# HV-PCB.net
KiCad netlist of a schematic drawn in EAGLE
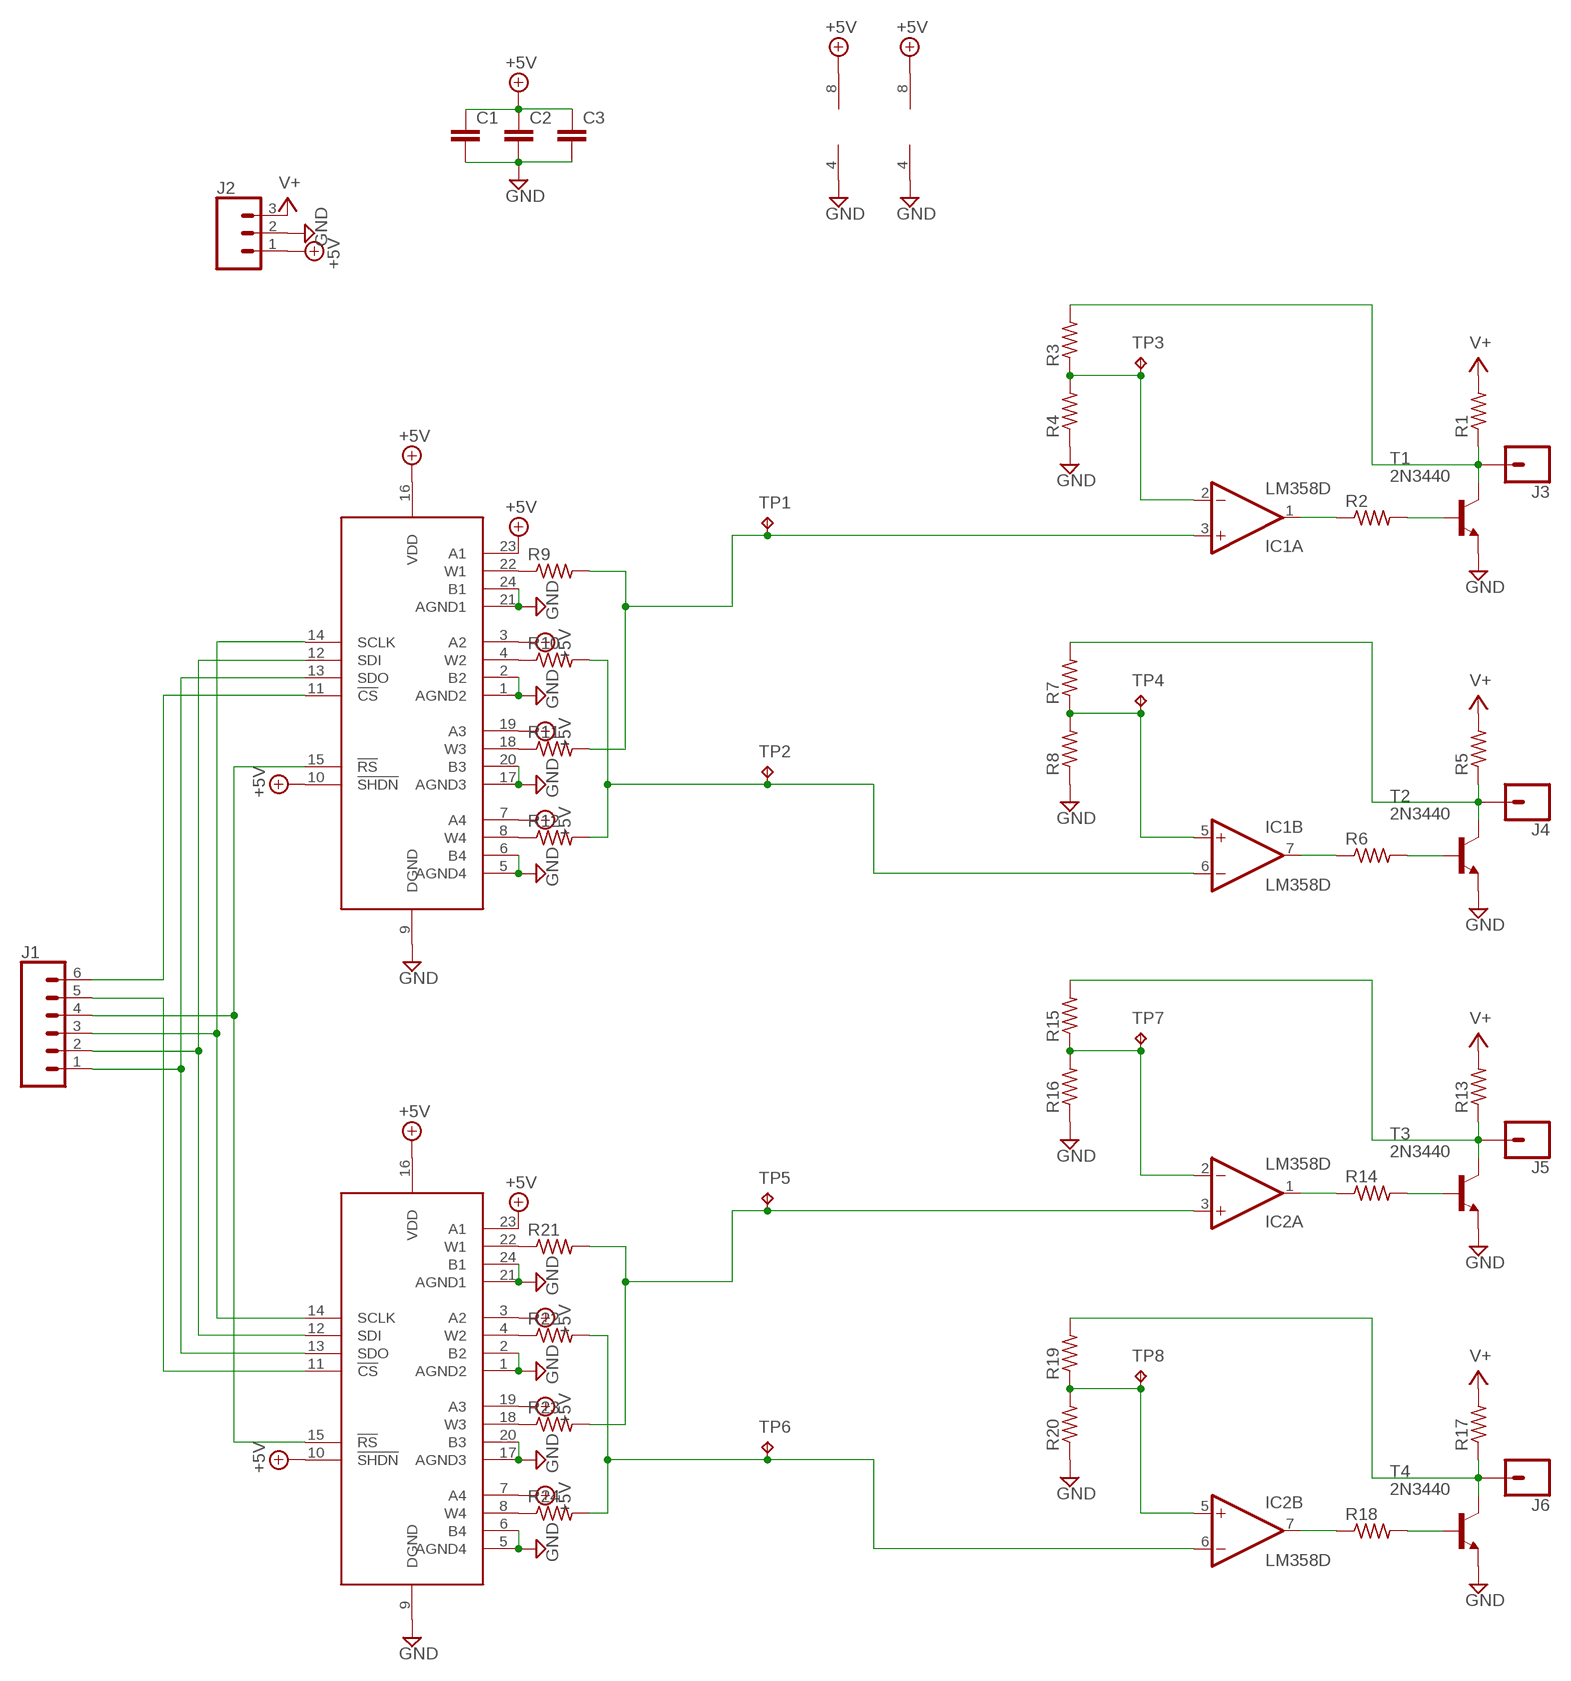
[diagram p0: schematic, sheet 1]

(export (version "E")
  (design (tool "Eeschema 10.0.6"))
  (components
    (comp (ref "C1")
      (value "C-EUC1206K")
      (footprint "eagle-import:C1206K")
      (libsource (lib "eagle-import") (part "C-EUC1206K"))
    )
    (comp (ref "C2")
      (value "C-EUC1206K")
      (footprint "eagle-import:C1206K")
      (libsource (lib "eagle-import") (part "C-EUC1206K"))
    )
    (comp (ref "C3")
      (value "C-EUC1206K")
      (footprint "eagle-import:C1206K")
      (libsource (lib "eagle-import") (part "C-EUC1206K"))
    )
    (comp (ref "IC1")
      (value "LM358D")
      (footprint "eagle-import:SO08")
      (libsource (lib "eagle-import") (part "LM358D"))
    )
    (comp (ref "IC2")
      (value "LM358D")
      (footprint "eagle-import:SO08")
      (libsource (lib "eagle-import") (part "LM358D"))
    )
    (comp (ref "J1")
      (value "CONN_06SILK_FEMALE_PTH")
      (footprint "eagle-import:1X06")
      (libsource (lib "eagle-import") (part "CONN_06SILK_FEMALE_PTH"))
    )
    (comp (ref "J2")
      (value "CONN_03")
      (footprint "eagle-import:1X03")
      (libsource (lib "eagle-import") (part "CONN_03"))
    )
    (comp (ref "J3")
      (value "CONN_01")
      (footprint "eagle-import:1X01")
      (libsource (lib "eagle-import") (part "CONN_01"))
    )
    (comp (ref "J4")
      (value "CONN_01")
      (footprint "eagle-import:1X01")
      (libsource (lib "eagle-import") (part "CONN_01"))
    )
    (comp (ref "J5")
      (value "CONN_01")
      (footprint "eagle-import:1X01")
      (libsource (lib "eagle-import") (part "CONN_01"))
    )
    (comp (ref "J6")
      (value "CONN_01")
      (footprint "eagle-import:1X01")
      (libsource (lib "eagle-import") (part "CONN_01"))
    )
    (comp (ref "R1")
      (value "R-US_M1206")
      (footprint "eagle-import:M1206")
      (libsource (lib "eagle-import") (part "R-US_M1206"))
    )
    (comp (ref "R2")
      (value "R-US_M1206")
      (footprint "eagle-import:M1206")
      (libsource (lib "eagle-import") (part "R-US_M1206"))
    )
    (comp (ref "R3")
      (value "R-US_M1206")
      (footprint "eagle-import:M1206")
      (libsource (lib "eagle-import") (part "R-US_M1206"))
    )
    (comp (ref "R4")
      (value "R-US_M1206")
      (footprint "eagle-import:M1206")
      (libsource (lib "eagle-import") (part "R-US_M1206"))
    )
    (comp (ref "R5")
      (value "R-US_M1206")
      (footprint "eagle-import:M1206")
      (libsource (lib "eagle-import") (part "R-US_M1206"))
    )
    (comp (ref "R6")
      (value "R-US_M1206")
      (footprint "eagle-import:M1206")
      (libsource (lib "eagle-import") (part "R-US_M1206"))
    )
    (comp (ref "R7")
      (value "R-US_M1206")
      (footprint "eagle-import:M1206")
      (libsource (lib "eagle-import") (part "R-US_M1206"))
    )
    (comp (ref "R8")
      (value "R-US_M1206")
      (footprint "eagle-import:M1206")
      (libsource (lib "eagle-import") (part "R-US_M1206"))
    )
    (comp (ref "R9")
      (value "R-US_M1206")
      (footprint "eagle-import:M1206")
      (libsource (lib "eagle-import") (part "R-US_M1206"))
    )
    (comp (ref "R10")
      (value "R-US_M1206")
      (footprint "eagle-import:M1206")
      (libsource (lib "eagle-import") (part "R-US_M1206"))
    )
    (comp (ref "R11")
      (value "R-US_M1206")
      (footprint "eagle-import:M1206")
      (libsource (lib "eagle-import") (part "R-US_M1206"))
    )
    (comp (ref "R12")
      (value "R-US_M1206")
      (footprint "eagle-import:M1206")
      (libsource (lib "eagle-import") (part "R-US_M1206"))
    )
    (comp (ref "R13")
      (value "R-US_M1206")
      (footprint "eagle-import:M1206")
      (libsource (lib "eagle-import") (part "R-US_M1206"))
    )
    (comp (ref "R14")
      (value "R-US_M1206")
      (footprint "eagle-import:M1206")
      (libsource (lib "eagle-import") (part "R-US_M1206"))
    )
    (comp (ref "R15")
      (value "R-US_M1206")
      (footprint "eagle-import:M1206")
      (libsource (lib "eagle-import") (part "R-US_M1206"))
    )
    (comp (ref "R16")
      (value "R-US_M1206")
      (footprint "eagle-import:M1206")
      (libsource (lib "eagle-import") (part "R-US_M1206"))
    )
    (comp (ref "R17")
      (value "R-US_M1206")
      (footprint "eagle-import:M1206")
      (libsource (lib "eagle-import") (part "R-US_M1206"))
    )
    (comp (ref "R18")
      (value "R-US_M1206")
      (footprint "eagle-import:M1206")
      (libsource (lib "eagle-import") (part "R-US_M1206"))
    )
    (comp (ref "R19")
      (value "R-US_M1206")
      (footprint "eagle-import:M1206")
      (libsource (lib "eagle-import") (part "R-US_M1206"))
    )
    (comp (ref "R20")
      (value "R-US_M1206")
      (footprint "eagle-import:M1206")
      (libsource (lib "eagle-import") (part "R-US_M1206"))
    )
    (comp (ref "R21")
      (value "R-US_M1206")
      (footprint "eagle-import:M1206")
      (libsource (lib "eagle-import") (part "R-US_M1206"))
    )
    (comp (ref "R22")
      (value "R-US_M1206")
      (footprint "eagle-import:M1206")
      (libsource (lib "eagle-import") (part "R-US_M1206"))
    )
    (comp (ref "R23")
      (value "R-US_M1206")
      (footprint "eagle-import:M1206")
      (libsource (lib "eagle-import") (part "R-US_M1206"))
    )
    (comp (ref "R24")
      (value "R-US_M1206")
      (footprint "eagle-import:M1206")
      (libsource (lib "eagle-import") (part "R-US_M1206"))
    )
    (comp (ref "T1")
      (value "2N3440")
      (footprint "eagle-import:TO5")
      (libsource (lib "eagle-import") (part "2N3440"))
    )
    (comp (ref "T2")
      (value "2N3440")
      (footprint "eagle-import:TO5")
      (libsource (lib "eagle-import") (part "2N3440"))
    )
    (comp (ref "T3")
      (value "2N3440")
      (footprint "eagle-import:TO5")
      (libsource (lib "eagle-import") (part "2N3440"))
    )
    (comp (ref "T4")
      (value "2N3440")
      (footprint "eagle-import:TO5")
      (libsource (lib "eagle-import") (part "2N3440"))
    )
    (comp (ref "TP1")
      (value "TPB1,27")
      (footprint "eagle-import:B1,27")
      (libsource (lib "eagle-import") (part "TPB1,27"))
    )
    (comp (ref "TP2")
      (value "TPB1,27")
      (footprint "eagle-import:B1,27")
      (libsource (lib "eagle-import") (part "TPB1,27"))
    )
    (comp (ref "TP3")
      (value "TPB1,27")
      (footprint "eagle-import:B1,27")
      (libsource (lib "eagle-import") (part "TPB1,27"))
    )
    (comp (ref "TP4")
      (value "TPB1,27")
      (footprint "eagle-import:B1,27")
      (libsource (lib "eagle-import") (part "TPB1,27"))
    )
    (comp (ref "TP5")
      (value "TPB1,27")
      (footprint "eagle-import:B1,27")
      (libsource (lib "eagle-import") (part "TPB1,27"))
    )
    (comp (ref "TP6")
      (value "TPB1,27")
      (footprint "eagle-import:B1,27")
      (libsource (lib "eagle-import") (part "TPB1,27"))
    )
    (comp (ref "TP7")
      (value "TPB1,27")
      (footprint "eagle-import:B1,27")
      (libsource (lib "eagle-import") (part "TPB1,27"))
    )
    (comp (ref "TP8")
      (value "TPB1,27")
      (footprint "eagle-import:B1,27")
      (libsource (lib "eagle-import") (part "TPB1,27"))
    )
    (comp (ref "U$1")
      (value "AD8403")
      (footprint "eagle-import:SO24L")
      (libsource (lib "eagle-import") (part "AD8403"))
    )
    (comp (ref "U$2")
      (value "AD8403")
      (footprint "eagle-import:SO24L")
      (libsource (lib "eagle-import") (part "AD8403"))
    )
  )
  (nets
    (net (code "1") (name "+5V") (class "Default")
      (node (ref "C1") (pin "1") (pinfunction "1_1") (pintype "passive"))
      (node (ref "C2") (pin "1") (pinfunction "1_1") (pintype "passive"))
      (node (ref "C3") (pin "1") (pinfunction "1_1") (pintype "passive"))
      (node (ref "IC1") (pin "8") (pinfunction "V+_8") (pintype "power_in"))
      (node (ref "IC2") (pin "8") (pinfunction "V+_8") (pintype "power_in"))
      (node (ref "J2") (pin "1") (pinfunction "1_1") (pintype "passive"))
      (node (ref "U$1") (pin "10") (pinfunction "~{SHDN}_10") (pintype "bidirectional"))
      (node (ref "U$1") (pin "16") (pinfunction "VDD_16") (pintype "bidirectional"))
      (node (ref "U$1") (pin "19") (pinfunction "A3_19") (pintype "bidirectional"))
      (node (ref "U$1") (pin "23") (pinfunction "A1_23") (pintype "bidirectional"))
      (node (ref "U$1") (pin "3") (pinfunction "A2_3") (pintype "bidirectional"))
      (node (ref "U$1") (pin "7") (pinfunction "A4_7") (pintype "bidirectional"))
      (node (ref "U$2") (pin "10") (pinfunction "~{SHDN}_10") (pintype "bidirectional"))
      (node (ref "U$2") (pin "16") (pinfunction "VDD_16") (pintype "bidirectional"))
      (node (ref "U$2") (pin "19") (pinfunction "A3_19") (pintype "bidirectional"))
      (node (ref "U$2") (pin "23") (pinfunction "A1_23") (pintype "bidirectional"))
      (node (ref "U$2") (pin "3") (pinfunction "A2_3") (pintype "bidirectional"))
      (node (ref "U$2") (pin "7") (pinfunction "A4_7") (pintype "bidirectional"))
    )
    (net (code "2") (name "GND") (class "Default")
      (node (ref "C1") (pin "2") (pinfunction "2_2") (pintype "passive"))
      (node (ref "C2") (pin "2") (pinfunction "2_2") (pintype "passive"))
      (node (ref "C3") (pin "2") (pinfunction "2_2") (pintype "passive"))
      (node (ref "IC1") (pin "4") (pinfunction "V-_4") (pintype "power_in"))
      (node (ref "IC2") (pin "4") (pinfunction "V-_4") (pintype "power_in"))
      (node (ref "J2") (pin "2") (pinfunction "2_2") (pintype "passive"))
      (node (ref "R16") (pin "1") (pinfunction "1_1") (pintype "passive"))
      (node (ref "R20") (pin "1") (pinfunction "1_1") (pintype "passive"))
      (node (ref "R4") (pin "1") (pinfunction "1_1") (pintype "passive"))
      (node (ref "R8") (pin "1") (pinfunction "1_1") (pintype "passive"))
      (node (ref "T1") (pin "1") (pinfunction "E_1") (pintype "passive"))
      (node (ref "T2") (pin "1") (pinfunction "E_1") (pintype "passive"))
      (node (ref "T3") (pin "1") (pinfunction "E_1") (pintype "passive"))
      (node (ref "T4") (pin "1") (pinfunction "E_1") (pintype "passive"))
      (node (ref "U$1") (pin "1") (pinfunction "AGND2_1") (pintype "bidirectional"))
      (node (ref "U$1") (pin "17") (pinfunction "AGND3_17") (pintype "bidirectional"))
      (node (ref "U$1") (pin "2") (pinfunction "B2_2") (pintype "bidirectional"))
      (node (ref "U$1") (pin "20") (pinfunction "B3_20") (pintype "bidirectional"))
      (node (ref "U$1") (pin "21") (pinfunction "AGND1_21") (pintype "bidirectional"))
      (node (ref "U$1") (pin "24") (pinfunction "B1_24") (pintype "bidirectional"))
      (node (ref "U$1") (pin "5") (pinfunction "AGND4_5") (pintype "bidirectional"))
      (node (ref "U$1") (pin "6") (pinfunction "B4_6") (pintype "bidirectional"))
      (node (ref "U$1") (pin "9") (pinfunction "DGND_9") (pintype "bidirectional"))
      (node (ref "U$2") (pin "1") (pinfunction "AGND2_1") (pintype "bidirectional"))
      (node (ref "U$2") (pin "17") (pinfunction "AGND3_17") (pintype "bidirectional"))
      (node (ref "U$2") (pin "2") (pinfunction "B2_2") (pintype "bidirectional"))
      (node (ref "U$2") (pin "20") (pinfunction "B3_20") (pintype "bidirectional"))
      (node (ref "U$2") (pin "21") (pinfunction "AGND1_21") (pintype "bidirectional"))
      (node (ref "U$2") (pin "24") (pinfunction "B1_24") (pintype "bidirectional"))
      (node (ref "U$2") (pin "5") (pinfunction "AGND4_5") (pintype "bidirectional"))
      (node (ref "U$2") (pin "6") (pinfunction "B4_6") (pintype "bidirectional"))
      (node (ref "U$2") (pin "9") (pinfunction "DGND_9") (pintype "bidirectional"))
    )
    (net (code "3") (name "Net-(IC1A-+IN)") (class "Default")
      (node (ref "IC1") (pin "3") (pinfunction "+IN_3") (pintype "input"))
      (node (ref "R11") (pin "2") (pinfunction "2_2") (pintype "passive"))
      (node (ref "R9") (pin "2") (pinfunction "2_2") (pintype "passive"))
      (node (ref "TP1") (pin "TP") (pinfunction "TP_TP") (pintype "input"))
    )
    (net (code "4") (name "Net-(IC1A--IN)") (class "Default")
      (node (ref "IC1") (pin "2") (pinfunction "-IN_2") (pintype "input"))
      (node (ref "R3") (pin "1") (pinfunction "1_1") (pintype "passive"))
      (node (ref "R4") (pin "2") (pinfunction "2_2") (pintype "passive"))
      (node (ref "TP3") (pin "TP") (pinfunction "TP_TP") (pintype "input"))
    )
    (net (code "5") (name "Net-(IC1A-OUT)") (class "Default")
      (node (ref "IC1") (pin "1") (pinfunction "OUT_1") (pintype "output"))
      (node (ref "R2") (pin "1") (pinfunction "1_1") (pintype "passive"))
    )
    (net (code "6") (name "Net-(IC1B-+IN)") (class "Default")
      (node (ref "IC1") (pin "5") (pinfunction "+IN_5") (pintype "input"))
      (node (ref "R7") (pin "1") (pinfunction "1_1") (pintype "passive"))
      (node (ref "R8") (pin "2") (pinfunction "2_2") (pintype "passive"))
      (node (ref "TP4") (pin "TP") (pinfunction "TP_TP") (pintype "input"))
    )
    (net (code "7") (name "Net-(IC1B--IN)") (class "Default")
      (node (ref "IC1") (pin "6") (pinfunction "-IN_6") (pintype "input"))
      (node (ref "R10") (pin "2") (pinfunction "2_2") (pintype "passive"))
      (node (ref "R12") (pin "2") (pinfunction "2_2") (pintype "passive"))
      (node (ref "TP2") (pin "TP") (pinfunction "TP_TP") (pintype "input"))
    )
    (net (code "8") (name "Net-(IC1B-OUT)") (class "Default")
      (node (ref "IC1") (pin "7") (pinfunction "OUT_7") (pintype "output"))
      (node (ref "R6") (pin "1") (pinfunction "1_1") (pintype "passive"))
    )
    (net (code "9") (name "Net-(IC2A-+IN)") (class "Default")
      (node (ref "IC2") (pin "3") (pinfunction "+IN_3") (pintype "input"))
      (node (ref "R21") (pin "2") (pinfunction "2_2") (pintype "passive"))
      (node (ref "R23") (pin "2") (pinfunction "2_2") (pintype "passive"))
      (node (ref "TP5") (pin "TP") (pinfunction "TP_TP") (pintype "input"))
    )
    (net (code "10") (name "Net-(IC2A--IN)") (class "Default")
      (node (ref "IC2") (pin "2") (pinfunction "-IN_2") (pintype "input"))
      (node (ref "R15") (pin "1") (pinfunction "1_1") (pintype "passive"))
      (node (ref "R16") (pin "2") (pinfunction "2_2") (pintype "passive"))
      (node (ref "TP7") (pin "TP") (pinfunction "TP_TP") (pintype "input"))
    )
    (net (code "11") (name "Net-(IC2A-OUT)") (class "Default")
      (node (ref "IC2") (pin "1") (pinfunction "OUT_1") (pintype "output"))
      (node (ref "R14") (pin "1") (pinfunction "1_1") (pintype "passive"))
    )
    (net (code "12") (name "Net-(IC2B-+IN)") (class "Default")
      (node (ref "IC2") (pin "5") (pinfunction "+IN_5") (pintype "input"))
      (node (ref "R19") (pin "1") (pinfunction "1_1") (pintype "passive"))
      (node (ref "R20") (pin "2") (pinfunction "2_2") (pintype "passive"))
      (node (ref "TP8") (pin "TP") (pinfunction "TP_TP") (pintype "input"))
    )
    (net (code "13") (name "Net-(IC2B--IN)") (class "Default")
      (node (ref "IC2") (pin "6") (pinfunction "-IN_6") (pintype "input"))
      (node (ref "R22") (pin "2") (pinfunction "2_2") (pintype "passive"))
      (node (ref "R24") (pin "2") (pinfunction "2_2") (pintype "passive"))
      (node (ref "TP6") (pin "TP") (pinfunction "TP_TP") (pintype "input"))
    )
    (net (code "14") (name "Net-(IC2B-OUT)") (class "Default")
      (node (ref "IC2") (pin "7") (pinfunction "OUT_7") (pintype "output"))
      (node (ref "R18") (pin "1") (pinfunction "1_1") (pintype "passive"))
    )
    (net (code "15") (name "Net-(T1-B)") (class "Default")
      (node (ref "R2") (pin "2") (pinfunction "2_2") (pintype "passive"))
      (node (ref "T1") (pin "2") (pinfunction "B_2") (pintype "passive"))
    )
    (net (code "16") (name "Net-(T1-C)") (class "Default")
      (node (ref "J3") (pin "1") (pinfunction "1_1") (pintype "passive"))
      (node (ref "R1") (pin "1") (pinfunction "1_1") (pintype "passive"))
      (node (ref "R3") (pin "2") (pinfunction "2_2") (pintype "passive"))
      (node (ref "T1") (pin "3") (pinfunction "C_3") (pintype "passive"))
    )
    (net (code "17") (name "Net-(T2-B)") (class "Default")
      (node (ref "R6") (pin "2") (pinfunction "2_2") (pintype "passive"))
      (node (ref "T2") (pin "2") (pinfunction "B_2") (pintype "passive"))
    )
    (net (code "18") (name "Net-(T2-C)") (class "Default")
      (node (ref "J4") (pin "1") (pinfunction "1_1") (pintype "passive"))
      (node (ref "R5") (pin "1") (pinfunction "1_1") (pintype "passive"))
      (node (ref "R7") (pin "2") (pinfunction "2_2") (pintype "passive"))
      (node (ref "T2") (pin "3") (pinfunction "C_3") (pintype "passive"))
    )
    (net (code "19") (name "Net-(T3-B)") (class "Default")
      (node (ref "R14") (pin "2") (pinfunction "2_2") (pintype "passive"))
      (node (ref "T3") (pin "2") (pinfunction "B_2") (pintype "passive"))
    )
    (net (code "20") (name "Net-(T3-C)") (class "Default")
      (node (ref "J5") (pin "1") (pinfunction "1_1") (pintype "passive"))
      (node (ref "R13") (pin "1") (pinfunction "1_1") (pintype "passive"))
      (node (ref "R15") (pin "2") (pinfunction "2_2") (pintype "passive"))
      (node (ref "T3") (pin "3") (pinfunction "C_3") (pintype "passive"))
    )
    (net (code "21") (name "Net-(T4-B)") (class "Default")
      (node (ref "R18") (pin "2") (pinfunction "2_2") (pintype "passive"))
      (node (ref "T4") (pin "2") (pinfunction "B_2") (pintype "passive"))
    )
    (net (code "22") (name "Net-(T4-C)") (class "Default")
      (node (ref "J6") (pin "1") (pinfunction "1_1") (pintype "passive"))
      (node (ref "R17") (pin "1") (pinfunction "1_1") (pintype "passive"))
      (node (ref "R19") (pin "2") (pinfunction "2_2") (pintype "passive"))
      (node (ref "T4") (pin "3") (pinfunction "C_3") (pintype "passive"))
    )
    (net (code "23") (name "Net-(U$1-SCLK)") (class "Default")
      (node (ref "J1") (pin "3") (pinfunction "3_3") (pintype "passive"))
      (node (ref "U$1") (pin "14") (pinfunction "SCLK_14") (pintype "bidirectional"))
      (node (ref "U$2") (pin "14") (pinfunction "SCLK_14") (pintype "bidirectional"))
    )
    (net (code "24") (name "Net-(U$1-SDI)") (class "Default")
      (node (ref "J1") (pin "2") (pinfunction "2_2") (pintype "passive"))
      (node (ref "U$1") (pin "12") (pinfunction "SDI_12") (pintype "bidirectional"))
      (node (ref "U$2") (pin "12") (pinfunction "SDI_12") (pintype "bidirectional"))
    )
    (net (code "25") (name "Net-(U$1-SDO)") (class "Default")
      (node (ref "J1") (pin "1") (pinfunction "1_1") (pintype "passive"))
      (node (ref "U$1") (pin "13") (pinfunction "SDO_13") (pintype "bidirectional"))
      (node (ref "U$2") (pin "13") (pinfunction "SDO_13") (pintype "bidirectional"))
    )
    (net (code "26") (name "Net-(U$1-W1)") (class "Default")
      (node (ref "R9") (pin "1") (pinfunction "1_1") (pintype "passive"))
      (node (ref "U$1") (pin "22") (pinfunction "W1_22") (pintype "bidirectional"))
    )
    (net (code "27") (name "Net-(U$1-W2)") (class "Default")
      (node (ref "R10") (pin "1") (pinfunction "1_1") (pintype "passive"))
      (node (ref "U$1") (pin "4") (pinfunction "W2_4") (pintype "bidirectional"))
    )
    (net (code "28") (name "Net-(U$1-W3)") (class "Default")
      (node (ref "R11") (pin "1") (pinfunction "1_1") (pintype "passive"))
      (node (ref "U$1") (pin "18") (pinfunction "W3_18") (pintype "bidirectional"))
    )
    (net (code "29") (name "Net-(U$1-W4)") (class "Default")
      (node (ref "R12") (pin "1") (pinfunction "1_1") (pintype "passive"))
      (node (ref "U$1") (pin "8") (pinfunction "W4_8") (pintype "bidirectional"))
    )
    (net (code "30") (name "Net-(U$1-~{CS})") (class "Default")
      (node (ref "J1") (pin "6") (pinfunction "6_6") (pintype "passive"))
      (node (ref "U$1") (pin "11") (pinfunction "~{CS}_11") (pintype "bidirectional"))
    )
    (net (code "31") (name "Net-(U$1-~{RS})") (class "Default")
      (node (ref "J1") (pin "4") (pinfunction "4_4") (pintype "passive"))
      (node (ref "U$1") (pin "15") (pinfunction "~{RS}_15") (pintype "bidirectional"))
      (node (ref "U$2") (pin "15") (pinfunction "~{RS}_15") (pintype "bidirectional"))
    )
    (net (code "32") (name "Net-(U$2-W1)") (class "Default")
      (node (ref "R21") (pin "1") (pinfunction "1_1") (pintype "passive"))
      (node (ref "U$2") (pin "22") (pinfunction "W1_22") (pintype "bidirectional"))
    )
    (net (code "33") (name "Net-(U$2-W2)") (class "Default")
      (node (ref "R22") (pin "1") (pinfunction "1_1") (pintype "passive"))
      (node (ref "U$2") (pin "4") (pinfunction "W2_4") (pintype "bidirectional"))
    )
    (net (code "34") (name "Net-(U$2-W3)") (class "Default")
      (node (ref "R23") (pin "1") (pinfunction "1_1") (pintype "passive"))
      (node (ref "U$2") (pin "18") (pinfunction "W3_18") (pintype "bidirectional"))
    )
    (net (code "35") (name "Net-(U$2-W4)") (class "Default")
      (node (ref "R24") (pin "1") (pinfunction "1_1") (pintype "passive"))
      (node (ref "U$2") (pin "8") (pinfunction "W4_8") (pintype "bidirectional"))
    )
    (net (code "36") (name "Net-(U$2-~{CS})") (class "Default")
      (node (ref "J1") (pin "5") (pinfunction "5_5") (pintype "passive"))
      (node (ref "U$2") (pin "11") (pinfunction "~{CS}_11") (pintype "bidirectional"))
    )
    (net (code "37") (name "V+") (class "Default")
      (node (ref "J2") (pin "3") (pinfunction "3_3") (pintype "passive"))
      (node (ref "R1") (pin "2") (pinfunction "2_2") (pintype "passive"))
      (node (ref "R13") (pin "2") (pinfunction "2_2") (pintype "passive"))
      (node (ref "R17") (pin "2") (pinfunction "2_2") (pintype "passive"))
      (node (ref "R5") (pin "2") (pinfunction "2_2") (pintype "passive"))
    )
  )
)
